# hamstackHAT.net
KiCad netlist of a schematic drawn in EAGLE
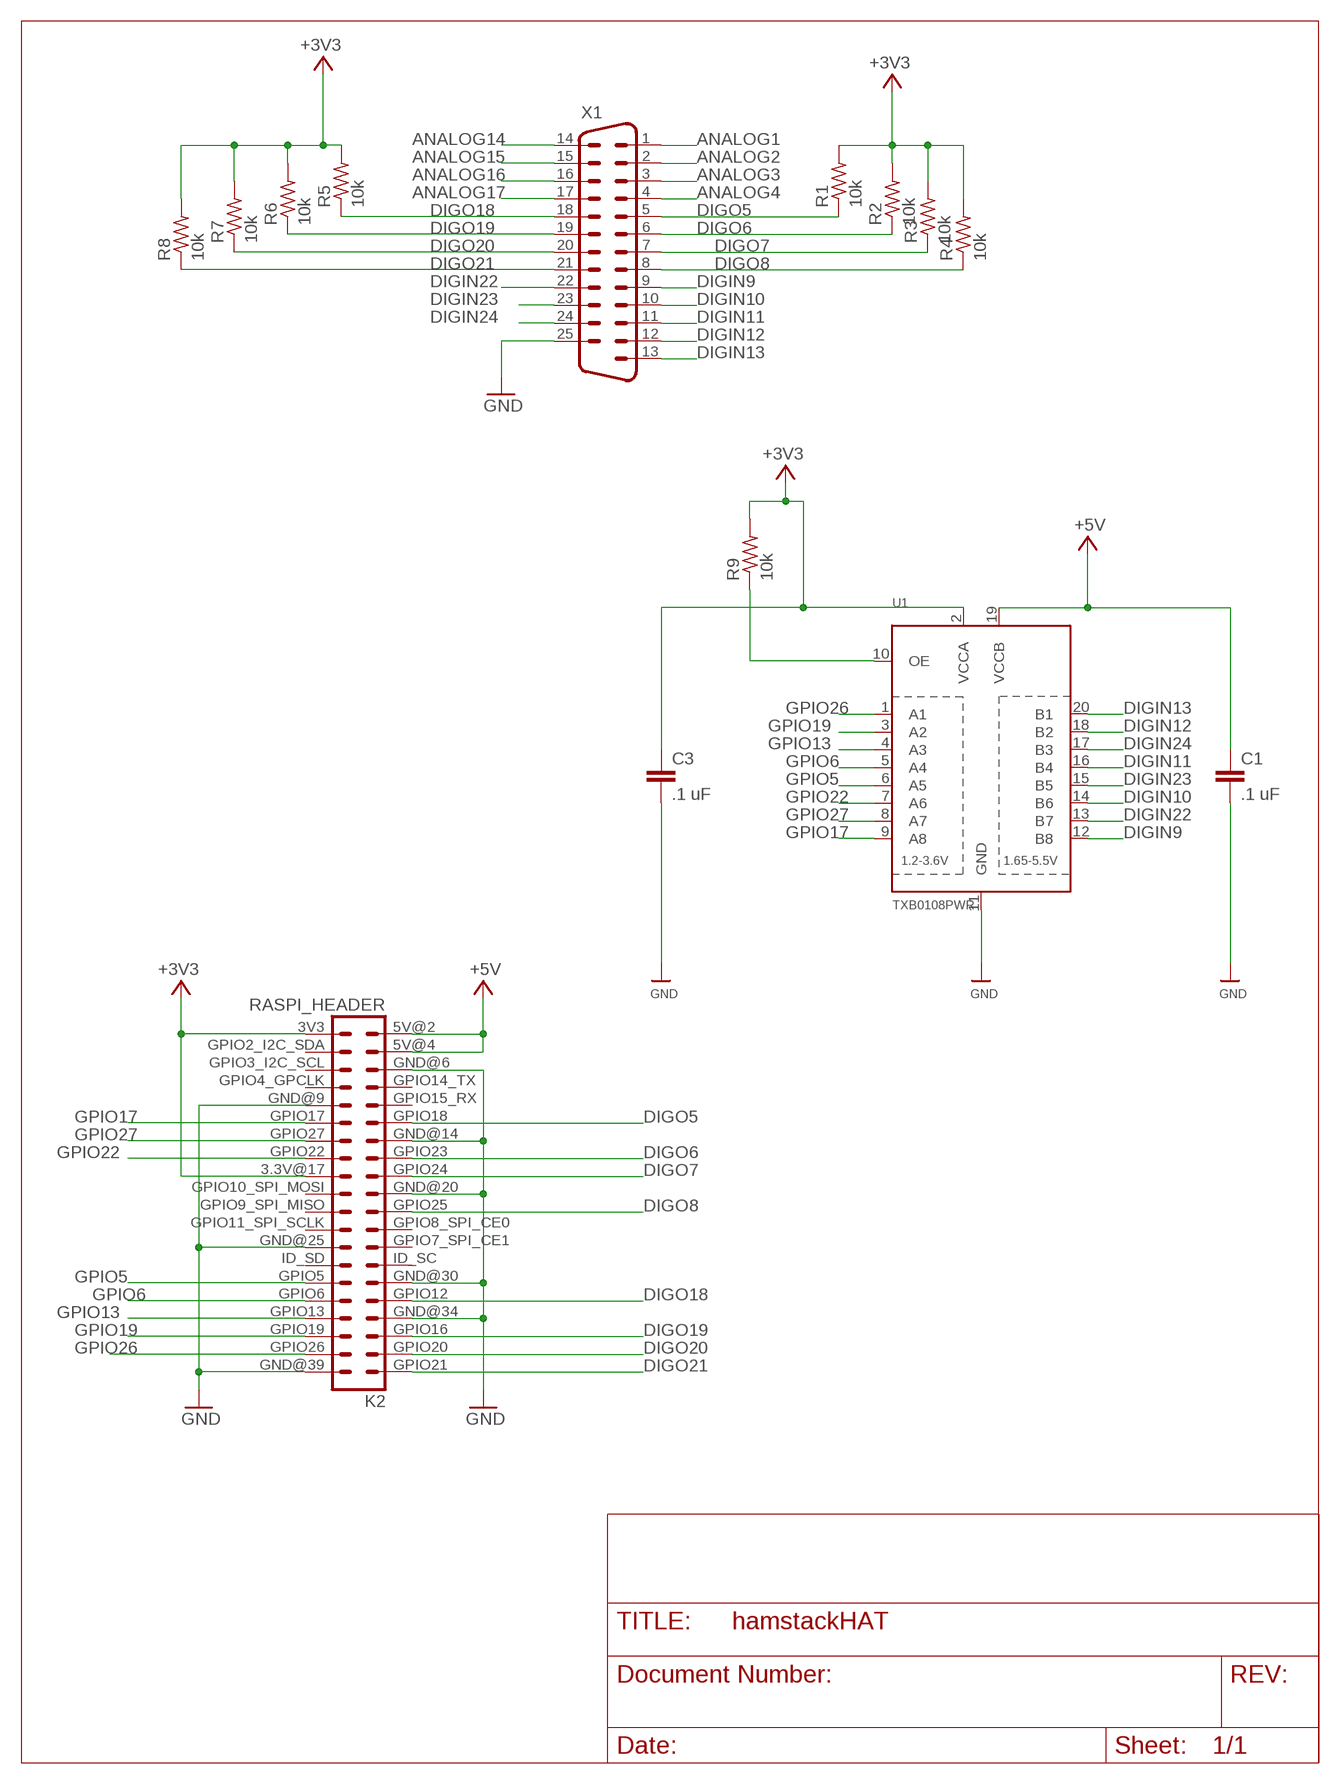
[diagram p0: schematic, sheet 1]

(export (version "E")
  (design (tool "Eeschema 10.0.6"))
  (components
    (comp (ref "C1")
      (value ".1 uF")
      (footprint "eagle-import:CAP-PTH-SMALL-KIT")
      (libsource (lib "eagle-import") (part "0.1UF-50V-20%(PTH)KIT-EZ"))
    )
    (comp (ref "C3")
      (value ".1 uF")
      (footprint "eagle-import:CAP-PTH-SMALL-KIT")
      (libsource (lib "eagle-import") (part "0.1UF-50V-20%(PTH)KIT-EZ"))
    )
    (comp (ref "K2")
      (value "RASPI_HEADER")
      (footprint "eagle-import:RASPI_HEADER")
      (libsource (lib "eagle-import") (part "RASPI_HEADER"))
    )
    (comp (ref "R1")
      (value "10k")
      (footprint "eagle-import:0207_10")
      (libsource (lib "eagle-import") (part "R-US_0207/10"))
    )
    (comp (ref "R2")
      (value "10k")
      (footprint "eagle-import:0207_10")
      (libsource (lib "eagle-import") (part "R-US_0207/10"))
    )
    (comp (ref "R3")
      (value "10k")
      (footprint "eagle-import:0207_10")
      (libsource (lib "eagle-import") (part "R-US_0207/10"))
    )
    (comp (ref "R4")
      (value "10k")
      (footprint "eagle-import:0207_10")
      (libsource (lib "eagle-import") (part "R-US_0207/10"))
    )
    (comp (ref "R5")
      (value "10k")
      (footprint "eagle-import:0207_10")
      (libsource (lib "eagle-import") (part "R-US_0207/10"))
    )
    (comp (ref "R6")
      (value "10k")
      (footprint "eagle-import:0207_10")
      (libsource (lib "eagle-import") (part "R-US_0207/10"))
    )
    (comp (ref "R7")
      (value "10k")
      (footprint "eagle-import:0207_10")
      (libsource (lib "eagle-import") (part "R-US_0207/10"))
    )
    (comp (ref "R8")
      (value "10k")
      (footprint "eagle-import:0207_10")
      (libsource (lib "eagle-import") (part "R-US_0207/10"))
    )
    (comp (ref "R9")
      (value "10k")
      (footprint "eagle-import:0207_10")
      (libsource (lib "eagle-import") (part "R-US_0207/10"))
    )
    (comp (ref "U1")
      (value "TXB0108PWR")
      (footprint "eagle-import:TSSOP20")
      (libsource (lib "eagle-import") (part "TXB0108PWR"))
    )
    (comp (ref "X1")
      (value "M25HP")
      (footprint "eagle-import:M25HP")
      (libsource (lib "eagle-import") (part "M25HP"))
    )
  )
  (nets
    (net (code "1") (name "+3V3") (class "Default")
      (node (ref "C3") (pin "1") (pinfunction "1_1") (pintype "passive"))
      (node (ref "K2") (pin "3.3V@17") (pinfunction "17_3.3V@17") (pintype "passive"))
      (node (ref "K2") (pin "3V3") (pinfunction "1_3V3") (pintype "passive"))
      (node (ref "R1") (pin "2") (pinfunction "2_2") (pintype "passive"))
      (node (ref "R2") (pin "2") (pinfunction "2_2") (pintype "passive"))
      (node (ref "R3") (pin "2") (pinfunction "2_2") (pintype "passive"))
      (node (ref "R4") (pin "2") (pinfunction "2_2") (pintype "passive"))
      (node (ref "R5") (pin "2") (pinfunction "2_2") (pintype "passive"))
      (node (ref "R6") (pin "2") (pinfunction "2_2") (pintype "passive"))
      (node (ref "R7") (pin "2") (pinfunction "2_2") (pintype "passive"))
      (node (ref "R8") (pin "2") (pinfunction "2_2") (pintype "passive"))
      (node (ref "R9") (pin "2") (pinfunction "2_2") (pintype "passive"))
      (node (ref "U1") (pin "2") (pinfunction "VCCA_2") (pintype "bidirectional"))
    )
    (net (code "2") (name "+5V") (class "Default")
      (node (ref "C1") (pin "1") (pinfunction "1_1") (pintype "passive"))
      (node (ref "K2") (pin "5V@2") (pinfunction "2_5V@2") (pintype "passive"))
      (node (ref "K2") (pin "5V@4") (pinfunction "4_5V@4") (pintype "passive"))
      (node (ref "U1") (pin "19") (pinfunction "VCCB_19") (pintype "bidirectional"))
    )
    (net (code "3") (name "/ANALOG1") (class "Default")
      (node (ref "X1") (pin "1") (pinfunction "1_1") (pintype "passive"))
    )
    (net (code "4") (name "/ANALOG2") (class "Default")
      (node (ref "X1") (pin "2") (pinfunction "2_2") (pintype "passive"))
    )
    (net (code "5") (name "/ANALOG3") (class "Default")
      (node (ref "X1") (pin "3") (pinfunction "3_3") (pintype "passive"))
    )
    (net (code "6") (name "/ANALOG4") (class "Default")
      (node (ref "X1") (pin "4") (pinfunction "4_4") (pintype "passive"))
    )
    (net (code "7") (name "/ANALOG14") (class "Default")
      (node (ref "X1") (pin "14") (pinfunction "14_14") (pintype "passive"))
    )
    (net (code "8") (name "/ANALOG15") (class "Default")
      (node (ref "X1") (pin "15") (pinfunction "15_15") (pintype "passive"))
    )
    (net (code "9") (name "/ANALOG16") (class "Default")
      (node (ref "X1") (pin "16") (pinfunction "16_16") (pintype "passive"))
    )
    (net (code "10") (name "/ANALOG17") (class "Default")
      (node (ref "X1") (pin "17") (pinfunction "17_17") (pintype "passive"))
    )
    (net (code "11") (name "/DIGIN9") (class "Default")
      (node (ref "U1") (pin "12") (pinfunction "B8_12") (pintype "bidirectional"))
      (node (ref "X1") (pin "9") (pinfunction "9_9") (pintype "passive"))
    )
    (net (code "12") (name "/DIGIN10") (class "Default")
      (node (ref "U1") (pin "14") (pinfunction "B6_14") (pintype "bidirectional"))
      (node (ref "X1") (pin "10") (pinfunction "10_10") (pintype "passive"))
    )
    (net (code "13") (name "/DIGIN11") (class "Default")
      (node (ref "U1") (pin "16") (pinfunction "B4_16") (pintype "bidirectional"))
      (node (ref "X1") (pin "11") (pinfunction "11_11") (pintype "passive"))
    )
    (net (code "14") (name "/DIGIN12") (class "Default")
      (node (ref "U1") (pin "18") (pinfunction "B2_18") (pintype "bidirectional"))
      (node (ref "X1") (pin "12") (pinfunction "12_12") (pintype "passive"))
    )
    (net (code "15") (name "/DIGIN13") (class "Default")
      (node (ref "U1") (pin "20") (pinfunction "B1_20") (pintype "bidirectional"))
      (node (ref "X1") (pin "13") (pinfunction "13_13") (pintype "passive"))
    )
    (net (code "16") (name "/DIGIN22") (class "Default")
      (node (ref "U1") (pin "13") (pinfunction "B7_13") (pintype "bidirectional"))
      (node (ref "X1") (pin "22") (pinfunction "22_22") (pintype "passive"))
    )
    (net (code "17") (name "/DIGIN23") (class "Default")
      (node (ref "U1") (pin "15") (pinfunction "B5_15") (pintype "bidirectional"))
      (node (ref "X1") (pin "23") (pinfunction "23_23") (pintype "passive"))
    )
    (net (code "18") (name "/DIGIN24") (class "Default")
      (node (ref "U1") (pin "17") (pinfunction "B3_17") (pintype "bidirectional"))
      (node (ref "X1") (pin "24") (pinfunction "24_24") (pintype "passive"))
    )
    (net (code "19") (name "/DIGO5") (class "Default")
      (node (ref "K2") (pin "GPIO18") (pinfunction "12_GPIO18") (pintype "passive"))
      (node (ref "R1") (pin "1") (pinfunction "1_1") (pintype "passive"))
      (node (ref "X1") (pin "5") (pinfunction "5_5") (pintype "passive"))
    )
    (net (code "20") (name "/DIGO6") (class "Default")
      (node (ref "K2") (pin "GPIO23") (pinfunction "16_GPIO23") (pintype "passive"))
      (node (ref "R2") (pin "1") (pinfunction "1_1") (pintype "passive"))
      (node (ref "X1") (pin "6") (pinfunction "6_6") (pintype "passive"))
    )
    (net (code "21") (name "/DIGO7") (class "Default")
      (node (ref "K2") (pin "GPIO24") (pinfunction "18_GPIO24") (pintype "passive"))
      (node (ref "R3") (pin "1") (pinfunction "1_1") (pintype "passive"))
      (node (ref "X1") (pin "7") (pinfunction "7_7") (pintype "passive"))
    )
    (net (code "22") (name "/DIGO8") (class "Default")
      (node (ref "K2") (pin "GPIO25") (pinfunction "22_GPIO25") (pintype "passive"))
      (node (ref "R4") (pin "1") (pinfunction "1_1") (pintype "passive"))
      (node (ref "X1") (pin "8") (pinfunction "8_8") (pintype "passive"))
    )
    (net (code "23") (name "/DIGO18") (class "Default")
      (node (ref "K2") (pin "GPIO12") (pinfunction "32_GPIO12") (pintype "passive"))
      (node (ref "R5") (pin "1") (pinfunction "1_1") (pintype "passive"))
      (node (ref "X1") (pin "18") (pinfunction "18_18") (pintype "passive"))
    )
    (net (code "24") (name "/DIGO19") (class "Default")
      (node (ref "K2") (pin "GPIO16") (pinfunction "36_GPIO16") (pintype "passive"))
      (node (ref "R6") (pin "1") (pinfunction "1_1") (pintype "passive"))
      (node (ref "X1") (pin "19") (pinfunction "19_19") (pintype "passive"))
    )
    (net (code "25") (name "/DIGO20") (class "Default")
      (node (ref "K2") (pin "GPIO20") (pinfunction "38_GPIO20") (pintype "passive"))
      (node (ref "R7") (pin "1") (pinfunction "1_1") (pintype "passive"))
      (node (ref "X1") (pin "20") (pinfunction "20_20") (pintype "passive"))
    )
    (net (code "26") (name "/DIGO21") (class "Default")
      (node (ref "K2") (pin "GPIO21") (pinfunction "GPIO21_GPIO21") (pintype "passive"))
      (node (ref "R8") (pin "1") (pinfunction "1_1") (pintype "passive"))
      (node (ref "X1") (pin "21") (pinfunction "21_21") (pintype "passive"))
    )
    (net (code "27") (name "/GPIO5") (class "Default")
      (node (ref "K2") (pin "GPIO5") (pinfunction "29_GPIO5") (pintype "passive"))
      (node (ref "U1") (pin "6") (pinfunction "A5_6") (pintype "bidirectional"))
    )
    (net (code "28") (name "/GPIO6") (class "Default")
      (node (ref "K2") (pin "GPIO6") (pinfunction "31_GPIO6") (pintype "passive"))
      (node (ref "U1") (pin "5") (pinfunction "A4_5") (pintype "bidirectional"))
    )
    (net (code "29") (name "/GPIO13") (class "Default")
      (node (ref "K2") (pin "GPIO13") (pinfunction "33_GPIO13") (pintype "passive"))
      (node (ref "U1") (pin "4") (pinfunction "A3_4") (pintype "bidirectional"))
    )
    (net (code "30") (name "/GPIO17") (class "Default")
      (node (ref "K2") (pin "GPIO17") (pinfunction "11_GPIO17") (pintype "passive"))
      (node (ref "U1") (pin "9") (pinfunction "A8_9") (pintype "bidirectional"))
    )
    (net (code "31") (name "/GPIO19") (class "Default")
      (node (ref "K2") (pin "GPIO19") (pinfunction "35_GPIO19") (pintype "passive"))
      (node (ref "U1") (pin "3") (pinfunction "A2_3") (pintype "bidirectional"))
    )
    (net (code "32") (name "/GPIO22") (class "Default")
      (node (ref "K2") (pin "GPIO22") (pinfunction "15_GPIO22") (pintype "passive"))
      (node (ref "U1") (pin "7") (pinfunction "A6_7") (pintype "bidirectional"))
    )
    (net (code "33") (name "/GPIO26") (class "Default")
      (node (ref "K2") (pin "GPIO26") (pinfunction "37_GPIO26") (pintype "passive"))
      (node (ref "U1") (pin "1") (pinfunction "A1_1") (pintype "bidirectional"))
    )
    (net (code "34") (name "/GPIO27") (class "Default")
      (node (ref "K2") (pin "GPIO27") (pinfunction "13_GPIO27") (pintype "passive"))
      (node (ref "U1") (pin "8") (pinfunction "A7_8") (pintype "bidirectional"))
    )
    (net (code "35") (name "GND") (class "Default")
      (node (ref "C1") (pin "2") (pinfunction "2_2") (pintype "passive"))
      (node (ref "C3") (pin "2") (pinfunction "2_2") (pintype "passive"))
      (node (ref "K2") (pin "GND@14") (pinfunction "14_GND@14") (pintype "passive"))
      (node (ref "K2") (pin "GND@20") (pinfunction "20_GND@20") (pintype "passive"))
      (node (ref "K2") (pin "GND@25") (pinfunction "25_GND@25") (pintype "passive"))
      (node (ref "K2") (pin "GND@30") (pinfunction "30_GND@30") (pintype "passive"))
      (node (ref "K2") (pin "GND@34") (pinfunction "34_GND@34") (pintype "passive"))
      (node (ref "K2") (pin "GND@39") (pinfunction "39_GND@39") (pintype "passive"))
      (node (ref "K2") (pin "GND@6") (pinfunction "6_GND@6") (pintype "passive"))
      (node (ref "K2") (pin "GND@9") (pinfunction "9_GND@9") (pintype "passive"))
      (node (ref "U1") (pin "11") (pinfunction "GND_11") (pintype "bidirectional"))
      (node (ref "X1") (pin "25") (pinfunction "25_25") (pintype "passive"))
    )
    (net (code "36") (name "Net-(U1-OE)") (class "Default")
      (node (ref "R9") (pin "1") (pinfunction "1_1") (pintype "passive"))
      (node (ref "U1") (pin "10") (pinfunction "OE_10") (pintype "bidirectional"))
    )
    (net (code "37") (name "unconnected-(K2-3-PadGPIO2_I2C_SDA)") (class "Default")
      (node (ref "K2") (pin "GPIO2_I2C_SDA") (pinfunction "3_GPIO2_I2C_SDA") (pintype "passive"))
    )
    (net (code "38") (name "unconnected-(K2-5-PadGPIO3_I2C_SCL)") (class "Default")
      (node (ref "K2") (pin "GPIO3_I2C_SCL") (pinfunction "5_GPIO3_I2C_SCL") (pintype "passive"))
    )
    (net (code "39") (name "unconnected-(K2-7-PadGPIO4_GPCLK)") (class "Default")
      (node (ref "K2") (pin "GPIO4_GPCLK") (pinfunction "7_GPIO4_GPCLK") (pintype "passive"))
    )
    (net (code "40") (name "unconnected-(K2-8-PadGPIO14_TX)") (class "Default")
      (node (ref "K2") (pin "GPIO14_TX") (pinfunction "8_GPIO14_TX") (pintype "passive"))
    )
    (net (code "41") (name "unconnected-(K2-10-PadGPIO15_RX)") (class "Default")
      (node (ref "K2") (pin "GPIO15_RX") (pinfunction "10_GPIO15_RX") (pintype "passive"))
    )
    (net (code "42") (name "unconnected-(K2-19-PadGPIO10_SPI_MOSI)") (class "Default")
      (node (ref "K2") (pin "GPIO10_SPI_MOSI") (pinfunction "19_GPIO10_SPI_MOSI") (pintype "passive"))
    )
    (net (code "43") (name "unconnected-(K2-21-PadGPIO9_SPI_MISO)") (class "Default")
      (node (ref "K2") (pin "GPIO9_SPI_MISO") (pinfunction "21_GPIO9_SPI_MISO") (pintype "passive"))
    )
    (net (code "44") (name "unconnected-(K2-23-PadGPIO11_SPI_SCLK)") (class "Default")
      (node (ref "K2") (pin "GPIO11_SPI_SCLK") (pinfunction "23_GPIO11_SPI_SCLK") (pintype "passive"))
    )
    (net (code "45") (name "unconnected-(K2-24-PadGPIO8_SPI_CE0)") (class "Default")
      (node (ref "K2") (pin "GPIO8_SPI_CE0") (pinfunction "24_GPIO8_SPI_CE0") (pintype "passive"))
    )
    (net (code "46") (name "unconnected-(K2-26-PadGPIO7_SPI_CE1)") (class "Default")
      (node (ref "K2") (pin "GPIO7_SPI_CE1") (pinfunction "26_GPIO7_SPI_CE1") (pintype "passive"))
    )
    (net (code "47") (name "unconnected-(K2-27-PadID_SD)") (class "Default")
      (node (ref "K2") (pin "ID_SD") (pinfunction "27_ID_SD") (pintype "passive"))
    )
    (net (code "48") (name "unconnected-(K2-28-PadID_SC)") (class "Default")
      (node (ref "K2") (pin "ID_SC") (pinfunction "28_ID_SC") (pintype "passive"))
    )
  )
)
